# SW6106_A_B_C_LED.net
KiCad netlist of a schematic drawn in Altium Designer
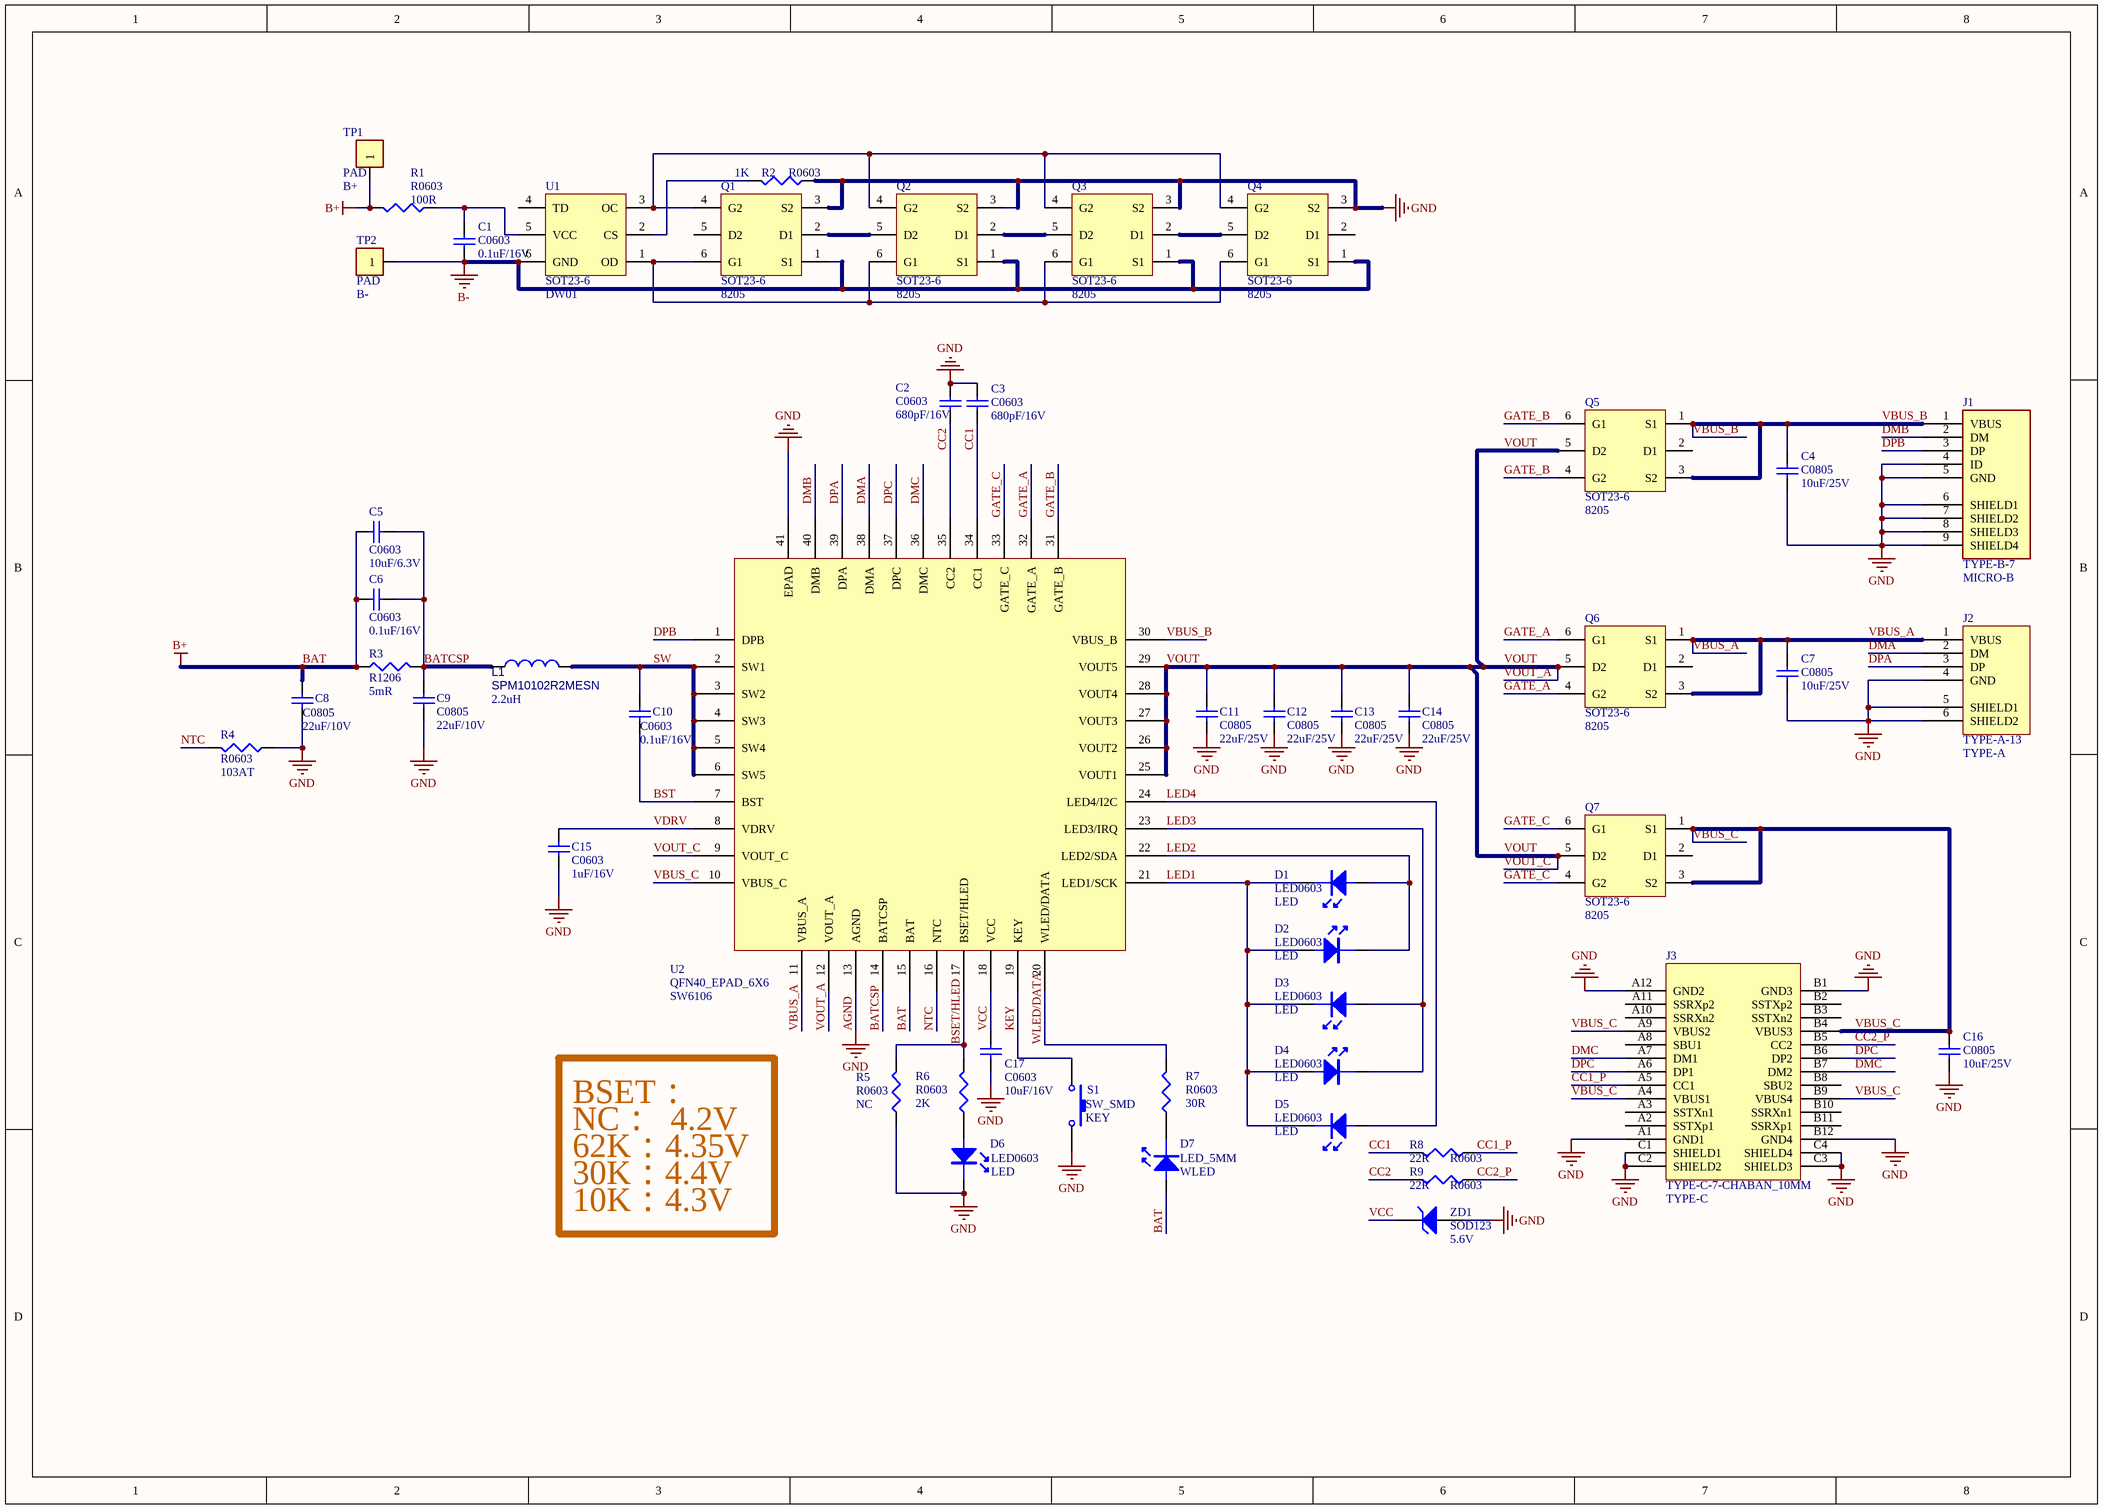
[diagram p0: SW6106+A+B+C+LED.SchDoc]

(export (version "E")
  (design (tool "Eeschema 10.0.6"))
  (components
    (comp (ref "C1")
      (value "C0603")
      (footprint "C0603")
      (description "Capacitor")
      (fields (field (name "ALTIUM_VALUE") "0.1uF/16V") (field (name "PUBLISHER") "Altium Limited"))
      (libsource (lib "*") (part "Cap"))
    )
    (comp (ref "C2")
      (value "C0603")
      (footprint "C0603")
      (description "Capacitor")
      (fields (field (name "ALTIUM_VALUE") "680pF/16V") (field (name "PUBLISHER") "Altium Limited"))
      (libsource (lib "*") (part "CAP0603"))
    )
    (comp (ref "C3")
      (value "C0603")
      (footprint "C0603")
      (description "Capacitor")
      (fields (field (name "ALTIUM_VALUE") "680pF/16V") (field (name "PUBLISHER") "Altium Limited"))
      (libsource (lib "*") (part "CAP0603"))
    )
    (comp (ref "C4")
      (value "C0805")
      (footprint "C0805")
      (description "Capacitor")
      (fields (field (name "ALTIUM_VALUE") "10uF/25V") (field (name "PUBLISHER") "Altium Limited"))
      (libsource (lib "*") (part "CAP0603"))
    )
    (comp (ref "C5")
      (value "C0603")
      (footprint "C0603")
      (description "Capacitor")
      (fields (field (name "ALTIUM_VALUE") "10uF/6.3V") (field (name "PUBLISHER") "Altium Limited"))
      (libsource (lib "*") (part "CAP0603"))
    )
    (comp (ref "C6")
      (value "C0603")
      (footprint "C0603")
      (description "Capacitor")
      (fields (field (name "ALTIUM_VALUE") "0.1uF/16V") (field (name "PUBLISHER") "Altium Limited"))
      (libsource (lib "*") (part "CAP0603"))
    )
    (comp (ref "C7")
      (value "C0805")
      (footprint "C0805")
      (description "Capacitor")
      (fields (field (name "ALTIUM_VALUE") "10uF/25V") (field (name "PUBLISHER") "Altium Limited"))
      (libsource (lib "*") (part "CAP0603"))
    )
    (comp (ref "C8")
      (value "C0805")
      (footprint "C0805")
      (description "Capacitor")
      (fields (field (name "ALTIUM_VALUE") "22uF/10V") (field (name "PUBLISHER") "Altium Limited"))
      (libsource (lib "*") (part "CAP0805"))
    )
    (comp (ref "C9")
      (value "C0805")
      (footprint "C0805")
      (description "Capacitor")
      (fields (field (name "ALTIUM_VALUE") "22uF/10V") (field (name "PUBLISHER") "Altium Limited"))
      (libsource (lib "*") (part "CAP0805"))
    )
    (comp (ref "C10")
      (value "C0603")
      (footprint "C0603")
      (description "Capacitor")
      (fields (field (name "ALTIUM_VALUE") "0.1uF/16V") (field (name "PUBLISHER") "Altium Limited"))
      (libsource (lib "*") (part "CAP0603"))
    )
    (comp (ref "C11")
      (value "C0805")
      (footprint "C0805")
      (description "Capacitor")
      (fields (field (name "ALTIUM_VALUE") "22uF/25V") (field (name "PUBLISHER") "Altium Limited"))
      (libsource (lib "*") (part "CAP0805"))
    )
    (comp (ref "C12")
      (value "C0805")
      (footprint "C0805")
      (description "Capacitor")
      (fields (field (name "ALTIUM_VALUE") "22uF/25V") (field (name "PUBLISHER") "Altium Limited"))
      (libsource (lib "*") (part "CAP0805"))
    )
    (comp (ref "C13")
      (value "C0805")
      (footprint "C0805")
      (description "Capacitor")
      (fields (field (name "ALTIUM_VALUE") "22uF/25V") (field (name "PUBLISHER") "Altium Limited"))
      (libsource (lib "*") (part "CAP0805"))
    )
    (comp (ref "C14")
      (value "C0805")
      (footprint "C0805")
      (description "Capacitor")
      (fields (field (name "ALTIUM_VALUE") "22uF/25V") (field (name "PUBLISHER") "Altium Limited"))
      (libsource (lib "*") (part "CAP0805"))
    )
    (comp (ref "C15")
      (value "C0603")
      (footprint "C0603")
      (description "Capacitor")
      (fields (field (name "ALTIUM_VALUE") "1uF/16V") (field (name "PUBLISHER") "Altium Limited"))
      (libsource (lib "*") (part "CAP0603"))
    )
    (comp (ref "C16")
      (value "C0805")
      (footprint "C0805")
      (description "Capacitor")
      (fields (field (name "ALTIUM_VALUE") "10uF/25V") (field (name "PUBLISHER") "Altium Limited"))
      (libsource (lib "*") (part "CAP0603"))
    )
    (comp (ref "C17")
      (value "C0603")
      (footprint "C0603")
      (description "Capacitor")
      (fields (field (name "ALTIUM_VALUE") "10uF/16V") (field (name "PUBLISHER") "Altium Limited"))
      (libsource (lib "*") (part "CAP0603"))
    )
    (comp (ref "D1") (value "LED") (footprint "LED0603") (libsource (lib "*") (part "LED")))
    (comp (ref "D2") (value "LED") (footprint "LED0603") (libsource (lib "*") (part "LED")))
    (comp (ref "D3") (value "LED") (footprint "LED0603") (libsource (lib "*") (part "LED")))
    (comp (ref "D4") (value "LED") (footprint "LED0603") (libsource (lib "*") (part "LED")))
    (comp (ref "D5") (value "LED") (footprint "LED0603") (libsource (lib "*") (part "LED")))
    (comp (ref "D6") (value "LED") (footprint "LED0603") (libsource (lib "*") (part "LED")))
    (comp (ref "D7")
      (value "WLED")
      (footprint "LED_5MM")
      (fields (field (name "FOOTPRINF") "LED_5MM") (field (name "Comment") "LED_5MM"))
      (libsource (lib "*") (part "LED"))
    )
    (comp (ref "J1")
      (value "MICRO-B")
      (footprint "TYPE-B-7")
      (fields (field (name "FOOTPRINTF") "TYPE-B-7") (field (name "Comment") "USB_MICRO_B"))
      (libsource (lib "*") (part "USB_MICRO_B"))
    )
    (comp (ref "J2")
      (value "TYPE-A")
      (footprint "TYPE-A-13")
      (fields (field (name "FOOTPRINF") "TYPE-A-13") (field (name "Comment") "TYPE-A-1"))
      (libsource (lib "*") (part "TYPE-A-1"))
    )
    (comp (ref "J3")
      (value "TYPE-C")
      (footprint "TYPE-C-7-CHABAN_10MM")
      (libsource (lib "*") (part "TYPE-C"))
    )
    (comp (ref "L1")
      (value "SPM10102R2MESN")
      (footprint "INDUCTOR_SPM1010")
      (fields (field (name "ALTIUM_VALUE") "2.2uH"))
      (libsource (lib "*") (part "INDUCTOR"))
    )
    (comp (ref "Q1")
      (value "8205")
      (footprint "SOT23-6")
      (fields (field (name "FOOTPRINF") "SOT23-6"))
      (libsource (lib "*") (part "8205B"))
    )
    (comp (ref "Q2")
      (value "8205")
      (footprint "SOT23-6")
      (fields (field (name "FOOTPRINF") "SOT23-6"))
      (libsource (lib "*") (part "8205B"))
    )
    (comp (ref "Q3")
      (value "8205")
      (footprint "SOT23-6")
      (fields (field (name "FOOTPRINF") "SOT23-6"))
      (libsource (lib "*") (part "8205B"))
    )
    (comp (ref "Q4")
      (value "8205")
      (footprint "SOT23-6")
      (fields (field (name "FOOTPRINF") "SOT23-6"))
      (libsource (lib "*") (part "8205B"))
    )
    (comp (ref "Q5")
      (value "8205")
      (footprint "SOT23-6")
      (fields (field (name "FOOTPRINF") "SOT23-6"))
      (libsource (lib "") (part "8205B_1"))
    )
    (comp (ref "Q6")
      (value "8205")
      (footprint "SOT23-6")
      (fields (field (name "FOOTPRINF") "SOT23-6"))
      (libsource (lib "") (part "8205B_1"))
    )
    (comp (ref "Q7")
      (value "8205")
      (footprint "SOT23-6")
      (fields (field (name "FOOTPRINF") "SOT23-6"))
      (libsource (lib "") (part "8205B_1"))
    )
    (comp (ref "R1")
      (value "R0603")
      (footprint "R0603")
      (description "Resistor")
      (fields (field (name "ALTIUM_VALUE") "100R") (field (name "PUBLISHER") "Altium Limited"))
      (libsource (lib "*") (part "Res3"))
    )
    (comp (ref "R2")
      (value "R0603")
      (footprint "R0603")
      (description "Resistor")
      (fields (field (name "ALTIUM_VALUE") "1K") (field (name "PUBLISHER") "Altium Limited"))
      (libsource (lib "*") (part "Res3"))
    )
    (comp (ref "R3")
      (value "R1206")
      (footprint "R1206")
      (description "Resistor")
      (fields (field (name "ALTIUM_VALUE") "5mR") (field (name "PUBLISHER") "Altium Limited"))
      (libsource (lib "*") (part "RES"))
    )
    (comp (ref "R4")
      (value "R0603")
      (footprint "R0603")
      (description "Resistor")
      (fields (field (name "ALTIUM_VALUE") "103AT") (field (name "PUBLISHER") "Altium Limited"))
      (libsource (lib "*") (part "RES"))
    )
    (comp (ref "R5")
      (value "R0603")
      (footprint "R0603")
      (description "Resistor")
      (fields (field (name "ALTIUM_VALUE") "NC") (field (name "PUBLISHER") "Altium Limited"))
      (libsource (lib "*") (part "RES"))
    )
    (comp (ref "R6")
      (value "R0603")
      (footprint "R0603")
      (description "Resistor")
      (fields (field (name "ALTIUM_VALUE") "2K") (field (name "PUBLISHER") "Altium Limited"))
      (libsource (lib "*") (part "RES"))
    )
    (comp (ref "R7")
      (value "R0603")
      (footprint "R0603")
      (description "Resistor")
      (fields (field (name "ALTIUM_VALUE") "30R") (field (name "PUBLISHER") "Altium Limited"))
      (libsource (lib "*") (part "RES"))
    )
    (comp (ref "R8")
      (value "R0603")
      (footprint "R0603")
      (description "Resistor")
      (fields (field (name "ALTIUM_VALUE") "22R") (field (name "PUBLISHER") "Altium Limited"))
      (libsource (lib "*") (part "RES"))
    )
    (comp (ref "R9")
      (value "R0603")
      (footprint "R0603")
      (description "Resistor")
      (fields (field (name "ALTIUM_VALUE") "22R") (field (name "PUBLISHER") "Altium Limited"))
      (libsource (lib "*") (part "RES"))
    )
    (comp (ref "S1")
      (value "KEY")
      (footprint "SW_SMD")
      (fields (field (name "FOOTPRINF") "SW_SMD"))
      (libsource (lib "*") (part "SW K"))
    )
    (comp (ref "TP1") (value "B+") (footprint "PAD") (libsource (lib "") (part "Test Point_1")))
    (comp (ref "TP2") (value "B-") (footprint "PAD") (libsource (lib "*") (part "Test Point")))
    (comp (ref "U1")
      (value "DW01")
      (footprint "SOT23-6")
      (fields (field (name "FOOTPRINF") "SOT23-6"))
      (libsource (lib "*") (part "DW01"))
    )
    (comp (ref "U2")
      (value "SW6106")
      (footprint "QFN40_EPAD_6X6")
      (libsource (lib "TEST") (part "SW6106_AFC"))
    )
    (comp (ref "ZD1")
      (value "SOD123")
      (footprint "SOD-123")
      (description "Zener Diode")
      (fields (field (name "ALTIUM_UNNAMED_1") "5.6V"))
      (libsource (lib "Miscellaneous Devices") (part "D Zener"))
    )
  )
  (nets
    (net (code "1") (name "/BATCSP") (class "Default")
      (node (ref "C5") (pin "2") (pinfunction "2_2") (pintype "passive"))
      (node (ref "C6") (pin "2") (pinfunction "2_2") (pintype "passive"))
      (node (ref "C9") (pin "2") (pinfunction "2_2") (pintype "passive"))
      (node (ref "L1") (pin "1") (pinfunction "1_1") (pintype "passive"))
      (node (ref "R3") (pin "2") (pinfunction "2_2") (pintype "passive"))
      (node (ref "U2") (pin "14") (pinfunction "BATCSP_14") (pintype "passive"))
    )
    (net (code "2") (name "/BSET{slash}HLED") (class "Default")
      (node (ref "R5") (pin "2") (pinfunction "2_2") (pintype "passive"))
      (node (ref "R6") (pin "2") (pinfunction "2_2") (pintype "passive"))
      (node (ref "U2") (pin "17") (pinfunction "BSET/HLED_17") (pintype "passive"))
    )
    (net (code "3") (name "/BST") (class "Default")
      (node (ref "C10") (pin "1") (pinfunction "1_1") (pintype "passive"))
      (node (ref "U2") (pin "7") (pinfunction "BST_7") (pintype "passive"))
    )
    (net (code "4") (name "/CC1") (class "Default")
      (node (ref "C3") (pin "1") (pinfunction "1_1") (pintype "passive"))
      (node (ref "R8") (pin "2") (pinfunction "2_2") (pintype "passive"))
      (node (ref "U2") (pin "34") (pinfunction "CC1_34") (pintype "passive"))
    )
    (net (code "5") (name "/CC1_P") (class "Default")
      (node (ref "J3") (pin "A5") (pinfunction "CC1_A5") (pintype "passive"))
      (node (ref "R8") (pin "1") (pinfunction "1_1") (pintype "passive"))
    )
    (net (code "6") (name "/CC2") (class "Default")
      (node (ref "C2") (pin "1") (pinfunction "1_1") (pintype "passive"))
      (node (ref "R9") (pin "2") (pinfunction "2_2") (pintype "passive"))
      (node (ref "U2") (pin "35") (pinfunction "CC2_35") (pintype "passive"))
    )
    (net (code "7") (name "/CC2_P") (class "Default")
      (node (ref "J3") (pin "B5") (pinfunction "CC2_B5") (pintype "passive"))
      (node (ref "R9") (pin "1") (pinfunction "1_1") (pintype "passive"))
    )
    (net (code "8") (name "/DMA") (class "Default")
      (node (ref "J2") (pin "2") (pinfunction "DM_2") (pintype "passive"))
      (node (ref "U2") (pin "38") (pinfunction "DMA_38") (pintype "passive"))
    )
    (net (code "9") (name "/DMB") (class "Default")
      (node (ref "J1") (pin "2") (pinfunction "DM_2") (pintype "passive"))
      (node (ref "U2") (pin "40") (pinfunction "DMB_40") (pintype "passive"))
    )
    (net (code "10") (name "/DMC") (class "Default")
      (node (ref "J3") (pin "A7") (pinfunction "DM1_A7") (pintype "passive"))
      (node (ref "J3") (pin "B7") (pinfunction "DM2_B7") (pintype "passive"))
      (node (ref "U2") (pin "36") (pinfunction "DMC_36") (pintype "passive"))
    )
    (net (code "11") (name "/DPA") (class "Default")
      (node (ref "J2") (pin "3") (pinfunction "DP_3") (pintype "passive"))
      (node (ref "U2") (pin "39") (pinfunction "DPA_39") (pintype "passive"))
    )
    (net (code "12") (name "/DPB") (class "Default")
      (node (ref "J1") (pin "3") (pinfunction "DP_3") (pintype "passive"))
      (node (ref "U2") (pin "1") (pinfunction "DPB_1") (pintype "passive"))
    )
    (net (code "13") (name "/DPC") (class "Default")
      (node (ref "J3") (pin "A6") (pinfunction "DP1_A6") (pintype "passive"))
      (node (ref "J3") (pin "B6") (pinfunction "DP2_B6") (pintype "passive"))
      (node (ref "U2") (pin "37") (pinfunction "DPC_37") (pintype "passive"))
    )
    (net (code "14") (name "/GATE_A") (class "Default")
      (node (ref "Q6") (pin "4") (pinfunction "G2_4") (pintype "passive"))
      (node (ref "Q6") (pin "6") (pinfunction "G1_6") (pintype "passive"))
      (node (ref "U2") (pin "32") (pinfunction "GATE_A_32") (pintype "passive"))
    )
    (net (code "15") (name "/GATE_B") (class "Default")
      (node (ref "Q5") (pin "4") (pinfunction "G2_4") (pintype "passive"))
      (node (ref "Q5") (pin "6") (pinfunction "G1_6") (pintype "passive"))
      (node (ref "U2") (pin "31") (pinfunction "GATE_B_31") (pintype "passive"))
    )
    (net (code "16") (name "/GATE_C") (class "Default")
      (node (ref "Q7") (pin "4") (pinfunction "G2_4") (pintype "passive"))
      (node (ref "Q7") (pin "6") (pinfunction "G1_6") (pintype "passive"))
      (node (ref "U2") (pin "33") (pinfunction "GATE_C_33") (pintype "passive"))
    )
    (net (code "17") (name "/KEY") (class "Default")
      (node (ref "S1") (pin "1") (pinfunction "1_1") (pintype "passive"))
      (node (ref "U2") (pin "19") (pinfunction "KEY_19") (pintype "passive"))
    )
    (net (code "18") (name "/LED1") (class "Default")
      (node (ref "D1") (pin "2") (pinfunction "K_2") (pintype "passive"))
      (node (ref "D2") (pin "1") (pinfunction "A_1") (pintype "passive"))
      (node (ref "D3") (pin "2") (pinfunction "K_2") (pintype "passive"))
      (node (ref "D4") (pin "1") (pinfunction "A_1") (pintype "passive"))
      (node (ref "D5") (pin "2") (pinfunction "K_2") (pintype "passive"))
      (node (ref "U2") (pin "21") (pinfunction "LED1/SCK_21") (pintype "passive"))
    )
    (net (code "19") (name "/LED2") (class "Default")
      (node (ref "D1") (pin "1") (pinfunction "A_1") (pintype "passive"))
      (node (ref "D2") (pin "2") (pinfunction "K_2") (pintype "passive"))
      (node (ref "U2") (pin "22") (pinfunction "LED2/SDA_22") (pintype "passive"))
    )
    (net (code "20") (name "/LED3") (class "Default")
      (node (ref "D3") (pin "1") (pinfunction "A_1") (pintype "passive"))
      (node (ref "D4") (pin "2") (pinfunction "K_2") (pintype "passive"))
      (node (ref "U2") (pin "23") (pinfunction "LED3/IRQ_23") (pintype "passive"))
    )
    (net (code "21") (name "/LED4") (class "Default")
      (node (ref "D5") (pin "1") (pinfunction "A_1") (pintype "passive"))
      (node (ref "U2") (pin "24") (pinfunction "LED4/I2C_24") (pintype "passive"))
    )
    (net (code "22") (name "/NTC") (class "Default")
      (node (ref "R4") (pin "2") (pinfunction "2_2") (pintype "passive"))
      (node (ref "U2") (pin "16") (pinfunction "NTC_16") (pintype "passive"))
    )
    (net (code "23") (name "/SW") (class "Default")
      (node (ref "C10") (pin "2") (pinfunction "2_2") (pintype "passive"))
      (node (ref "L1") (pin "2") (pinfunction "2_2") (pintype "passive"))
      (node (ref "U2") (pin "2") (pinfunction "SW1_2") (pintype "passive"))
      (node (ref "U2") (pin "3") (pinfunction "SW2_3") (pintype "passive"))
      (node (ref "U2") (pin "4") (pinfunction "SW3_4") (pintype "passive"))
      (node (ref "U2") (pin "5") (pinfunction "SW4_5") (pintype "passive"))
      (node (ref "U2") (pin "6") (pinfunction "SW5_6") (pintype "passive"))
    )
    (net (code "24") (name "/VBUS_A") (class "Default")
      (node (ref "C7") (pin "2") (pinfunction "2_2") (pintype "passive"))
      (node (ref "J2") (pin "1") (pinfunction "VBUS_1") (pintype "passive"))
      (node (ref "Q6") (pin "1") (pinfunction "S1_1") (pintype "passive"))
      (node (ref "Q6") (pin "3") (pinfunction "S2_3") (pintype "passive"))
      (node (ref "U2") (pin "11") (pinfunction "VBUS_A_11") (pintype "passive"))
    )
    (net (code "25") (name "/VBUS_B") (class "Default")
      (node (ref "C4") (pin "2") (pinfunction "2_2") (pintype "passive"))
      (node (ref "J1") (pin "1") (pinfunction "VBUS_1") (pintype "passive"))
      (node (ref "Q5") (pin "1") (pinfunction "S1_1") (pintype "passive"))
      (node (ref "Q5") (pin "3") (pinfunction "S2_3") (pintype "passive"))
      (node (ref "U2") (pin "30") (pinfunction "VBUS_B_30") (pintype "passive"))
    )
    (net (code "26") (name "/VBUS_C") (class "Default")
      (node (ref "C16") (pin "2") (pinfunction "2_2") (pintype "passive"))
      (node (ref "J3") (pin "A4") (pinfunction "VBUS1_A4") (pintype "passive"))
      (node (ref "J3") (pin "A9") (pinfunction "VBUS2_A9") (pintype "passive"))
      (node (ref "J3") (pin "B4") (pinfunction "VBUS3_B4") (pintype "passive"))
      (node (ref "J3") (pin "B9") (pinfunction "VBUS4_B9") (pintype "passive"))
      (node (ref "Q7") (pin "1") (pinfunction "S1_1") (pintype "passive"))
      (node (ref "Q7") (pin "3") (pinfunction "S2_3") (pintype "passive"))
      (node (ref "U2") (pin "10") (pinfunction "VBUS_C_10") (pintype "passive"))
    )
    (net (code "27") (name "/VCC") (class "Default")
      (node (ref "C17") (pin "2") (pinfunction "2_2") (pintype "passive"))
      (node (ref "U2") (pin "18") (pinfunction "VCC_18") (pintype "passive"))
      (node (ref "ZD1") (pin "2") (pinfunction "K_2") (pintype "passive"))
    )
    (net (code "28") (name "/VDRV") (class "Default")
      (node (ref "C15") (pin "2") (pinfunction "2_2") (pintype "passive"))
      (node (ref "U2") (pin "8") (pinfunction "VDRV_8") (pintype "passive"))
    )
    (net (code "29") (name "/VOUT") (class "Default")
      (node (ref "C11") (pin "2") (pinfunction "2_2") (pintype "passive"))
      (node (ref "C12") (pin "2") (pinfunction "2_2") (pintype "passive"))
      (node (ref "C13") (pin "2") (pinfunction "2_2") (pintype "passive"))
      (node (ref "C14") (pin "2") (pinfunction "2_2") (pintype "passive"))
      (node (ref "Q5") (pin "5") (pinfunction "D2_5") (pintype "passive"))
      (node (ref "Q6") (pin "5") (pinfunction "D2_5") (pintype "passive"))
      (node (ref "Q7") (pin "5") (pinfunction "D2_5") (pintype "passive"))
      (node (ref "U2") (pin "12") (pinfunction "VOUT_A_12") (pintype "passive"))
      (node (ref "U2") (pin "25") (pinfunction "VOUT1_25") (pintype "passive"))
      (node (ref "U2") (pin "26") (pinfunction "VOUT2_26") (pintype "passive"))
      (node (ref "U2") (pin "27") (pinfunction "VOUT3_27") (pintype "passive"))
      (node (ref "U2") (pin "28") (pinfunction "VOUT4_28") (pintype "passive"))
      (node (ref "U2") (pin "29") (pinfunction "VOUT5_29") (pintype "passive"))
      (node (ref "U2") (pin "9") (pinfunction "VOUT_C_9") (pintype "passive"))
    )
    (net (code "30") (name "/WLED{slash}DATA") (class "Default")
      (node (ref "R7") (pin "2") (pinfunction "2_2") (pintype "passive"))
      (node (ref "U2") (pin "20") (pinfunction "WLED/DATA_20") (pintype "passive"))
    )
    (net (code "31") (name "B+") (class "Default")
      (node (ref "C5") (pin "1") (pinfunction "1_1") (pintype "passive"))
      (node (ref "C6") (pin "1") (pinfunction "1_1") (pintype "passive"))
      (node (ref "C8") (pin "2") (pinfunction "2_2") (pintype "passive"))
      (node (ref "D7") (pin "1") (pinfunction "A_1") (pintype "passive"))
      (node (ref "R1") (pin "2") (pinfunction "2_2") (pintype "passive"))
      (node (ref "R3") (pin "1") (pinfunction "1_1") (pintype "passive"))
      (node (ref "TP1") (pin "1") (pinfunction "1_1") (pintype "passive"))
      (node (ref "U2") (pin "15") (pinfunction "BAT_15") (pintype "passive"))
    )
    (net (code "32") (name "B-") (class "Default")
      (node (ref "C1") (pin "1") (pinfunction "1_1") (pintype "passive"))
      (node (ref "Q1") (pin "1") (pinfunction "S1_1") (pintype "passive"))
      (node (ref "Q2") (pin "1") (pinfunction "S1_1") (pintype "passive"))
      (node (ref "Q3") (pin "1") (pinfunction "S1_1") (pintype "passive"))
      (node (ref "Q4") (pin "1") (pinfunction "S1_1") (pintype "passive"))
      (node (ref "TP2") (pin "1") (pinfunction "1_1") (pintype "passive"))
      (node (ref "U1") (pin "6") (pinfunction "GND_6") (pintype "passive"))
    )
    (net (code "33") (name "GND") (class "Default")
      (node (ref "C11") (pin "1") (pinfunction "1_1") (pintype "passive"))
      (node (ref "C12") (pin "1") (pinfunction "1_1") (pintype "passive"))
      (node (ref "C13") (pin "1") (pinfunction "1_1") (pintype "passive"))
      (node (ref "C14") (pin "1") (pinfunction "1_1") (pintype "passive"))
      (node (ref "C15") (pin "1") (pinfunction "1_1") (pintype "passive"))
      (node (ref "C16") (pin "1") (pinfunction "1_1") (pintype "passive"))
      (node (ref "C17") (pin "1") (pinfunction "1_1") (pintype "passive"))
      (node (ref "C2") (pin "2") (pinfunction "2_2") (pintype "passive"))
      (node (ref "C3") (pin "2") (pinfunction "2_2") (pintype "passive"))
      (node (ref "C4") (pin "1") (pinfunction "1_1") (pintype "passive"))
      (node (ref "C7") (pin "1") (pinfunction "1_1") (pintype "passive"))
      (node (ref "C8") (pin "1") (pinfunction "1_1") (pintype "passive"))
      (node (ref "C9") (pin "1") (pinfunction "1_1") (pintype "passive"))
      (node (ref "D6") (pin "2") (pinfunction "K_2") (pintype "passive"))
      (node (ref "J1") (pin "4") (pinfunction "ID_4") (pintype "passive"))
      (node (ref "J1") (pin "5") (pinfunction "GND_5") (pintype "passive"))
      (node (ref "J1") (pin "6") (pinfunction "SHIELD1_6") (pintype "passive"))
      (node (ref "J1") (pin "7") (pinfunction "SHIELD2_7") (pintype "passive"))
      (node (ref "J1") (pin "8") (pinfunction "SHIELD3_8") (pintype "passive"))
      (node (ref "J1") (pin "9") (pinfunction "SHIELD4_9") (pintype "passive"))
      (node (ref "J2") (pin "4") (pinfunction "GND_4") (pintype "passive"))
      (node (ref "J2") (pin "5") (pinfunction "SHIELD1_5") (pintype "passive"))
      (node (ref "J2") (pin "6") (pinfunction "SHIELD2_6") (pintype "passive"))
      (node (ref "J3") (pin "A1") (pinfunction "GND1_A1") (pintype "passive"))
      (node (ref "J3") (pin "A12") (pinfunction "GND2_A12") (pintype "passive"))
      (node (ref "J3") (pin "B1") (pinfunction "GND3_B1") (pintype "passive"))
      (node (ref "J3") (pin "B12") (pinfunction "GND4_B12") (pintype "passive"))
      (node (ref "J3") (pin "C1") (pinfunction "SHIELD1_C1") (pintype "passive"))
      (node (ref "J3") (pin "C2") (pinfunction "SHIELD2_C2") (pintype "passive"))
      (node (ref "J3") (pin "C3") (pinfunction "SHIELD3_C3") (pintype "passive"))
      (node (ref "J3") (pin "C4") (pinfunction "SHIELD4_C4") (pintype "passive"))
      (node (ref "Q1") (pin "3") (pinfunction "S2_3") (pintype "passive"))
      (node (ref "Q2") (pin "3") (pinfunction "S2_3") (pintype "passive"))
      (node (ref "Q3") (pin "3") (pinfunction "S2_3") (pintype "passive"))
      (node (ref "Q4") (pin "3") (pinfunction "S2_3") (pintype "passive"))
      (node (ref "R2") (pin "1") (pinfunction "1_1") (pintype "passive"))
      (node (ref "R4") (pin "1") (pinfunction "1_1") (pintype "passive"))
      (node (ref "R5") (pin "1") (pinfunction "1_1") (pintype "passive"))
      (node (ref "S1") (pin "2") (pinfunction "2_2") (pintype "passive"))
      (node (ref "U2") (pin "13") (pinfunction "AGND_13") (pintype "passive"))
      (node (ref "U2") (pin "41") (pinfunction "EPAD_41") (pintype "passive"))
      (node (ref "ZD1") (pin "1") (pinfunction "A_1") (pintype "passive"))
    )
    (net (code "34") (name "Net-(D6-A)") (class "Default")
      (node (ref "D6") (pin "1") (pinfunction "A_1") (pintype "passive"))
      (node (ref "R6") (pin "1") (pinfunction "1_1") (pintype "passive"))
    )
    (net (code "35") (name "Net-(D7-K)") (class "Default")
      (node (ref "D7") (pin "2") (pinfunction "K_2") (pintype "passive"))
      (node (ref "R7") (pin "1") (pinfunction "1_1") (pintype "passive"))
    )
    (net (code "36") (name "Net-(Q1-D1)") (class "Default")
      (node (ref "Q1") (pin "2") (pinfunction "D1_2") (pintype "passive"))
      (node (ref "Q2") (pin "5") (pinfunction "D2_5") (pintype "passive"))
    )
    (net (code "37") (name "Net-(Q1-G1)") (class "Default")
      (node (ref "Q1") (pin "6") (pinfunction "G1_6") (pintype "passive"))
      (node (ref "Q2") (pin "6") (pinfunction "G1_6") (pintype "passive"))
      (node (ref "Q3") (pin "6") (pinfunction "G1_6") (pintype "passive"))
      (node (ref "Q4") (pin "6") (pinfunction "G1_6") (pintype "passive"))
      (node (ref "U1") (pin "1") (pinfunction "OD_1") (pintype "passive"))
    )
    (net (code "38") (name "Net-(Q1-G2)") (class "Default")
      (node (ref "Q1") (pin "4") (pinfunction "G2_4") (pintype "passive"))
      (node (ref "Q2") (pin "4") (pinfunction "G2_4") (pintype "passive"))
      (node (ref "Q3") (pin "4") (pinfunction "G2_4") (pintype "passive"))
      (node (ref "Q4") (pin "4") (pinfunction "G2_4") (pintype "passive"))
      (node (ref "U1") (pin "3") (pinfunction "OC_3") (pintype "passive"))
    )
    (net (code "39") (name "Net-(Q2-D1)") (class "Default")
      (node (ref "Q2") (pin "2") (pinfunction "D1_2") (pintype "passive"))
      (node (ref "Q3") (pin "5") (pinfunction "D2_5") (pintype "passive"))
    )
    (net (code "40") (name "Net-(Q3-D1)") (class "Default")
      (node (ref "Q3") (pin "2") (pinfunction "D1_2") (pintype "passive"))
      (node (ref "Q4") (pin "5") (pinfunction "D2_5") (pintype "passive"))
    )
    (net (code "41") (name "Net-(U1-CS)") (class "Default")
      (node (ref "R2") (pin "2") (pinfunction "2_2") (pintype "passive"))
      (node (ref "U1") (pin "2") (pinfunction "CS_2") (pintype "passive"))
    )
    (net (code "42") (name "Net-(U1-VCC)") (class "Default")
      (node (ref "C1") (pin "2") (pinfunction "2_2") (pintype "passive"))
      (node (ref "R1") (pin "1") (pinfunction "1_1") (pintype "passive"))
      (node (ref "U1") (pin "5") (pinfunction "VCC_5") (pintype "passive"))
    )
    (net (code "43") (name "unconnected-(J3-SBU1-PadA8)") (class "Default")
      (node (ref "J3") (pin "A8") (pinfunction "SBU1_A8") (pintype "passive"))
    )
    (net (code "44") (name "unconnected-(J3-SBU2-PadB8)") (class "Default")
      (node (ref "J3") (pin "B8") (pinfunction "SBU2_B8") (pintype "passive"))
    )
    (net (code "45") (name "unconnected-(J3-SSRXn1-PadB10)") (class "Default")
      (node (ref "J3") (pin "B10") (pinfunction "SSRXn1_B10") (pintype "passive"))
    )
    (net (code "46") (name "unconnected-(J3-SSRXn2-PadA10)") (class "Default")
      (node (ref "J3") (pin "A10") (pinfunction "SSRXn2_A10") (pintype "passive"))
    )
    (net (code "47") (name "unconnected-(J3-SSRXp1-PadB11)") (class "Default")
      (node (ref "J3") (pin "B11") (pinfunction "SSRXp1_B11") (pintype "passive"))
    )
    (net (code "48") (name "unconnected-(J3-SSRXp2-PadA11)") (class "Default")
      (node (ref "J3") (pin "A11") (pinfunction "SSRXp2_A11") (pintype "passive"))
    )
    (net (code "49") (name "unconnected-(J3-SSTXn1-PadA3)") (class "Default")
      (node (ref "J3") (pin "A3") (pinfunction "SSTXn1_A3") (pintype "passive"))
    )
    (net (code "50") (name "unconnected-(J3-SSTXn2-PadB3)") (class "Default")
      (node (ref "J3") (pin "B3") (pinfunction "SSTXn2_B3") (pintype "passive"))
    )
    (net (code "51") (name "unconnected-(J3-SSTXp1-PadA2)") (class "Default")
      (node (ref "J3") (pin "A2") (pinfunction "SSTXp1_A2") (pintype "passive"))
    )
    (net (code "52") (name "unconnected-(J3-SSTXp2-PadB2)") (class "Default")
      (node (ref "J3") (pin "B2") (pinfunction "SSTXp2_B2") (pintype "passive"))
    )
    (net (code "53") (name "unconnected-(Q1-D2-Pad5)") (class "Default")
      (node (ref "Q1") (pin "5") (pinfunction "D2_5") (pintype "passive"))
    )
    (net (code "54") (name "unconnected-(Q4-D1-Pad2)") (class "Default")
      (node (ref "Q4") (pin "2") (pinfunction "D1_2") (pintype "passive"))
    )
    (net (code "55") (name "unconnected-(Q5-D1-Pad2)") (class "Default")
      (node (ref "Q5") (pin "2") (pinfunction "D1_2") (pintype "passive"))
    )
    (net (code "56") (name "unconnected-(Q6-D1-Pad2)") (class "Default")
      (node (ref "Q6") (pin "2") (pinfunction "D1_2") (pintype "passive"))
    )
    (net (code "57") (name "unconnected-(Q7-D1-Pad2)") (class "Default")
      (node (ref "Q7") (pin "2") (pinfunction "D1_2") (pintype "passive"))
    )
    (net (code "58") (name "unconnected-(U1-TD-Pad4)") (class "Default")
      (node (ref "U1") (pin "4") (pinfunction "TD_4") (pintype "passive"))
    )
  )
)
